# 03_-_PWR_IN.net
KiCad netlist of a schematic drawn in Altium Designer
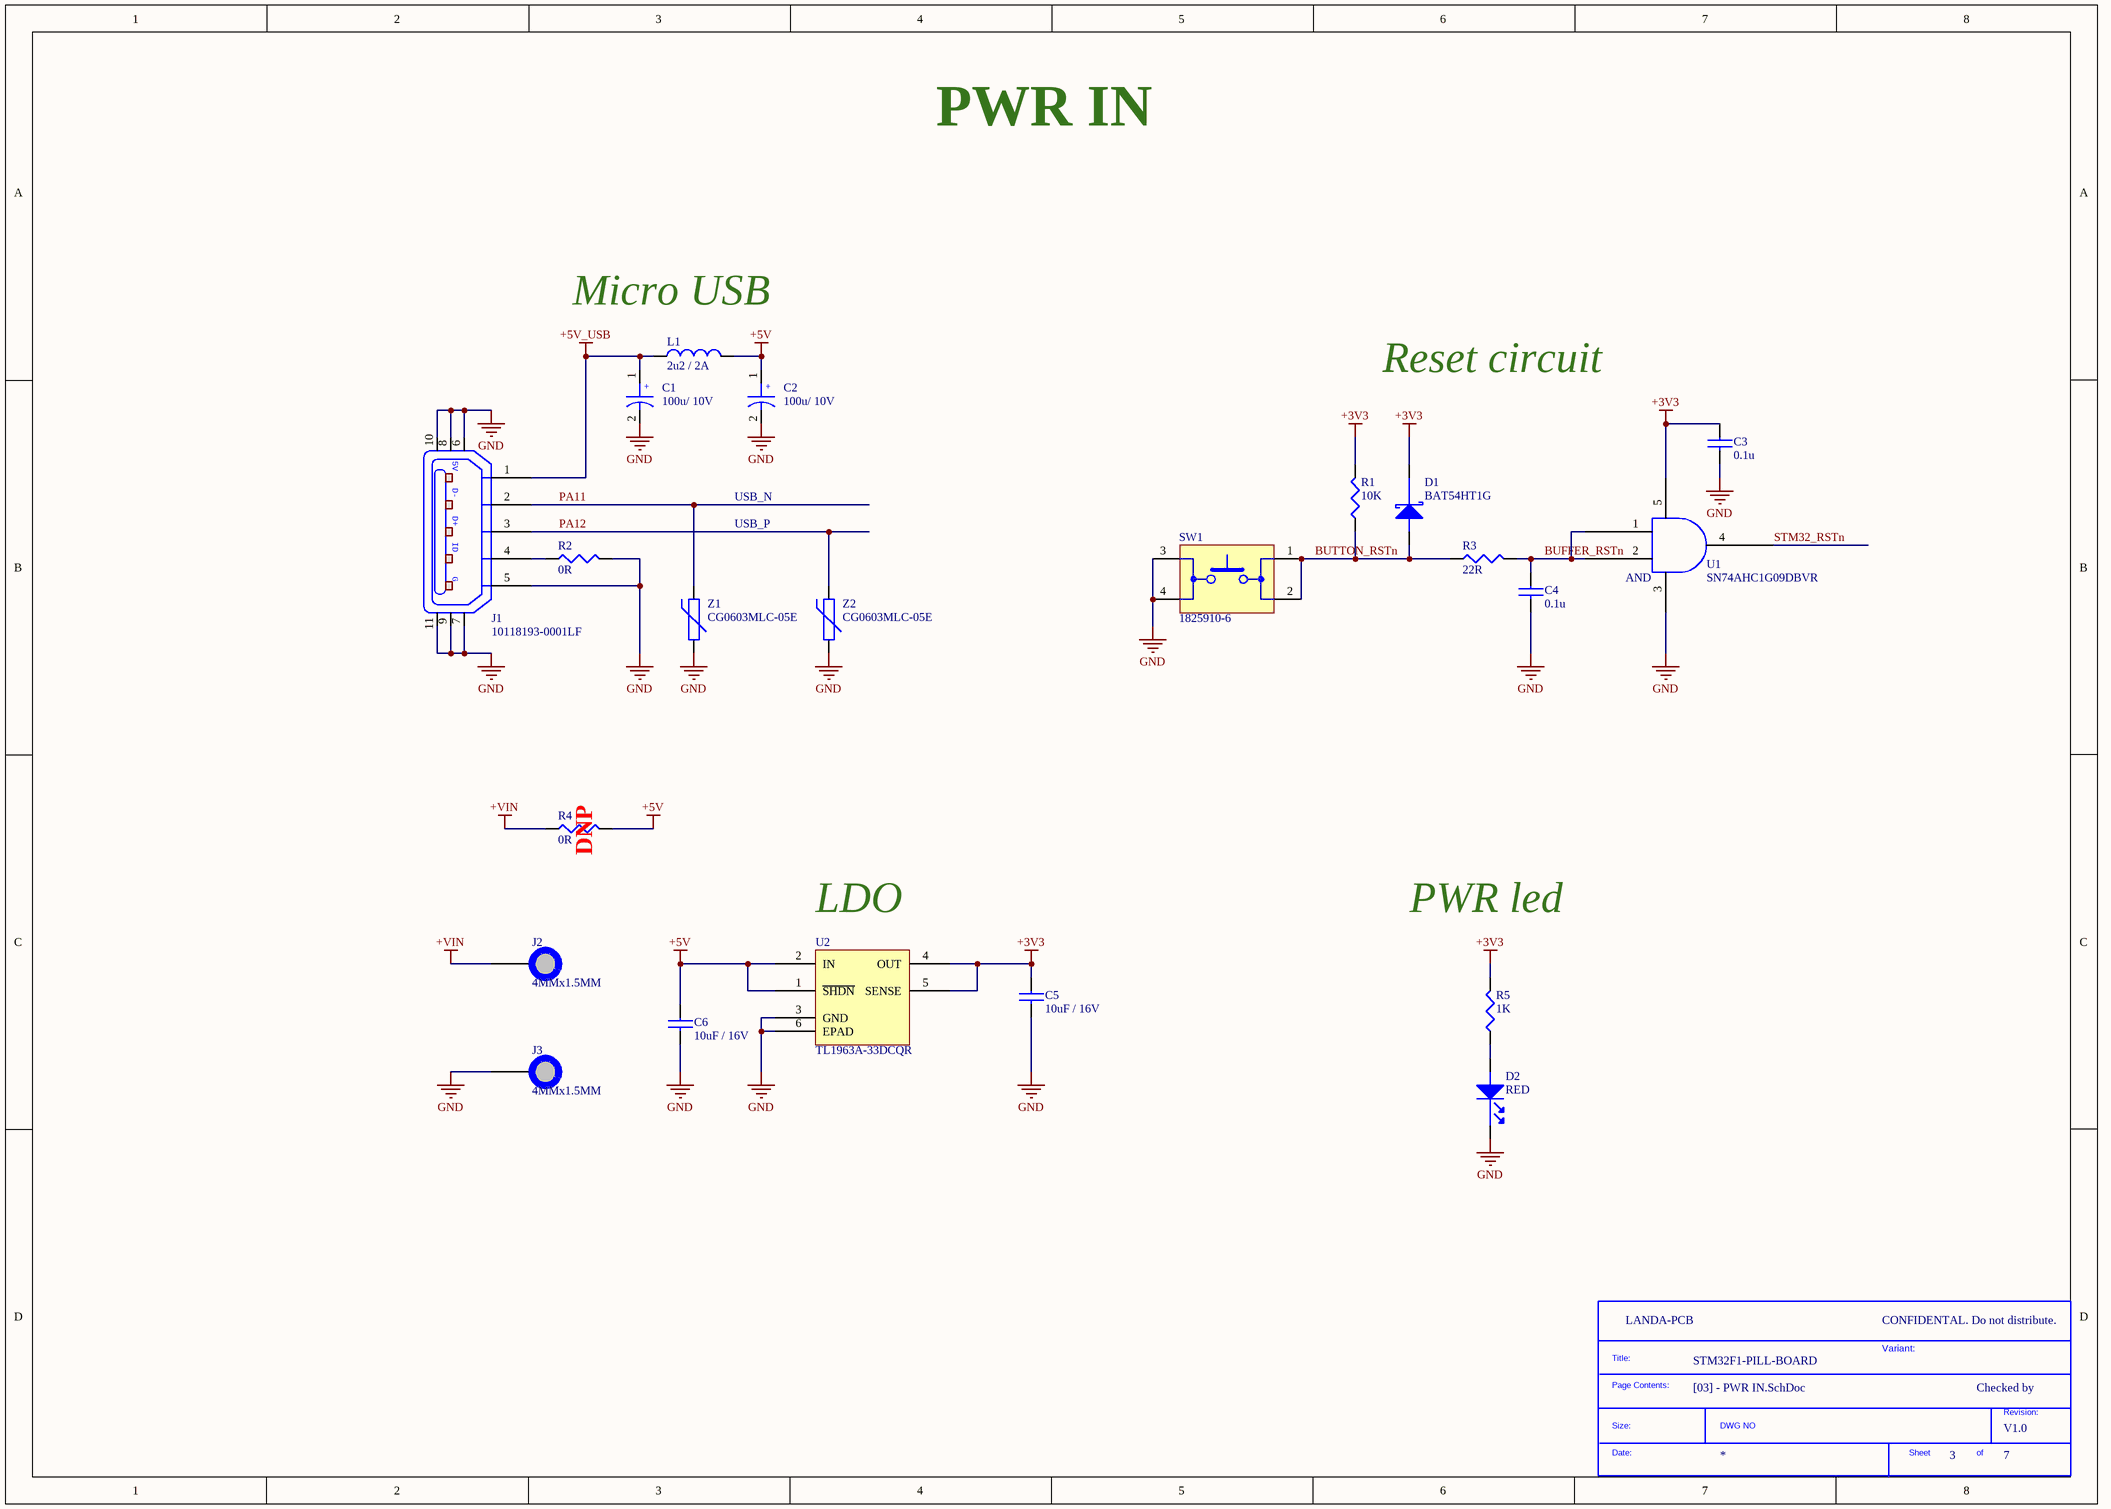
[diagram p0: [03] - PWR IN.SchDoc]

(export (version "E")
  (design (tool "Eeschema 10.0.6"))
  (components
    (comp (ref "C1")
      (value "100u/ 10V")
      (footprint "STM32-PILL-PCB:C_ALU_C_SIZE")
      (description "CAP ALUM 100uF 10V 20% (5 X 5.4mm) SMD")
      (fields
        (field (name "MANUFACTURER") "Panasonic")
        (field (name "MANUFACTURER PART NUMBER") "EEE-1AA101WR")
      )
      (libsource (lib "STM32-PILL-SHC") (part "EEE-1AA101WR"))
    )
    (comp (ref "C2")
      (value "100u/ 10V")
      (footprint "STM32-PILL-PCB:C_ALU_C_SIZE")
      (description "CAP ALUM 100uF 10V 20% (5 X 5.4mm) SMD")
      (fields
        (field (name "MANUFACTURER") "Panasonic")
        (field (name "MANUFACTURER PART NUMBER") "EEE-1AA101WR")
      )
      (libsource (lib "STM32-PILL-SHC") (part "EEE-1AA101WR"))
    )
    (comp (ref "C3")
      (value "0.1u")
      (footprint "STM32-PILL-PCB:C0805")
      (description "CAP CER 0.1UF 50V 10% X7R 0805")
      (fields
        (field (name "MANUFACTURER") "TDK")
        (field (name "MANUFACTURER PART NUMBER") "C2012X7R1H104K085AA")
      )
      (libsource (lib "STM32-PILL-SHC") (part "C2012X7R1H104K085AA"))
    )
    (comp (ref "C4")
      (value "0.1u")
      (footprint "STM32-PILL-PCB:C0805")
      (description "CAP CER 0.1UF 50V 10% X7R 0805")
      (fields
        (field (name "MANUFACTURER") "TDK")
        (field (name "MANUFACTURER PART NUMBER") "C2012X7R1H104K085AA")
      )
      (libsource (lib "STM32-PILL-SHC") (part "C2012X7R1H104K085AA"))
    )
    (comp (ref "C5")
      (value "10uF / 16V")
      (footprint "STM32-PILL-PCB:C0805")
      (description "CAP CER 10 µF, 16 V, 0805, ± 20%, X5R")
      (fields
        (field (name "MANUFACTURER") "TDK")
        (field (name "MANUFACTURER PART NUMBER") "C2012X5R1C106M085AC")
      )
      (libsource (lib "STM32-PILL-SHC") (part "C2012X5R1C106M085AC"))
    )
    (comp (ref "C6")
      (value "10uF / 16V")
      (footprint "STM32-PILL-PCB:C0805")
      (description "CAP CER 10 µF, 16 V, 0805, ± 20%, X5R")
      (fields
        (field (name "MANUFACTURER") "TDK")
        (field (name "MANUFACTURER PART NUMBER") "C2012X5R1C106M085AC")
      )
      (libsource (lib "STM32-PILL-SHC") (part "C2012X5R1C106M085AC"))
    )
    (comp (ref "D1")
      (value "BAT54HT1G")
      (footprint "STM32-PILL-PCB:SOD323")
      (description "DIODE SCHOTTKY 30V 0.2A SOD323")
      (fields (field (name "MANUFACTURER") "ON Semiconductor / Fairchild"))
      (libsource (lib "STM32-PILL-SHC") (part "BAT54HT1G"))
    )
    (comp (ref "D2")
      (value "RED")
      (footprint "STM32-PILL-PCB:LED-0805")
      (description "LED RED 630NM 0805")
      (fields
        (field (name "MANUFACTURER") "Vishay Lite-On")
        (field (name "MANUFACTURER PART NUMBER") "LTST-C170EKT")
      )
      (libsource (lib "STM32-PILL-SHC") (part "LTST-C170EKT"))
    )
    (comp (ref "J1")
      (value "10118193-0001LF")
      (footprint "STM32-PILL-PCB:USB_10118193")
      (description "CONN USB MICRO B RECPT SMT R/A")
      (fields (field (name "MANUFACTURER") "Amphenol FCI"))
      (libsource (lib "STM32-PILL-SHC") (part "10118193-0001LF"))
    )
    (comp (ref "J2")
      (value "4MMx1.5MM")
      (footprint "PAD_WITH_HOLE_4MMx1.5MM")
      (description "Pad with a hole 4mm x 1.5mm")
      (libsource (lib "STM32-PILL-SHC") (part "PAD_WITH_HOLE_4MMx1.5MM"))
    )
    (comp (ref "J3")
      (value "4MMx1.5MM")
      (footprint "PAD_WITH_HOLE_4MMx1.5MM")
      (description "Pad with a hole 4mm x 1.5mm")
      (libsource (lib "STM32-PILL-SHC") (part "PAD_WITH_HOLE_4MMx1.5MM"))
    )
    (comp (ref "L1")
      (value "2u2 / 2A")
      (footprint "STM32-PILL-PCB:C1210_IND")
      (description "FIXED IND 2.2UH 2A 80 MOHM SMD")
      (fields
        (field (name "MANUFACTURER") "KEMET")
        (field (name "MANUFACTURER PART NUMBER") "L1210R2R2MDWIT")
      )
      (libsource (lib "STM32-PILL-SHC") (part "L1210R2R2MDWIT"))
    )
    (comp (ref "R1")
      (value "10K")
      (footprint "STM32-PILL-PCB:R0805")
      (description "RES 10K OHM 1% 1/8W 0805")
      (fields
        (field (name "MANUFACTURER") "Yageo")
        (field (name "MANUFACTURER PART NUMBER") "RC0805FR-0710KL")
      )
      (libsource (lib "STM32-PILL-SHC") (part "RC0805FR-0710KL"))
    )
    (comp (ref "R2")
      (value "0R")
      (footprint "STM32-PILL-PCB:R0805")
      (description "RES 0.0 OHMS, 125 mW, 0805")
      (fields
        (field (name "MANUFACTURER") "Yageo")
        (field (name "MANUFACTURER PART NUMBER") "RC0805JR-070RL")
      )
      (libsource (lib "STM32-PILL-SHC") (part "RC0805JR-070RL"))
    )
    (comp (ref "R3")
      (value "22R")
      (footprint "STM32-PILL-PCB:R0805")
      (description "RES 22 OHM 1% 1/8W 0805")
      (fields
        (field (name "MANUFACTURER") "Yageo")
        (field (name "MANUFACTURER PART NUMBER") "RC0805FR-0722RL")
      )
      (libsource (lib "STM32-PILL-SHC") (part "RC0805FR-0722RL"))
    )
    (comp (ref "R4")
      (value "0R")
      (footprint "STM32-PILL-PCB:R0805")
      (description "RES 0.0 OHMS, 125 mW, 0805")
      (fields
        (field (name "MANUFACTURER") "Yageo")
        (field (name "MANUFACTURER PART NUMBER") "RC0805JR-070RL")
      )
      (libsource (lib "STM32-PILL-SHC") (part "RC0805JR-070RL"))
    )
    (comp (ref "R5")
      (value "1K")
      (footprint "STM32-PILL-PCB:R0805")
      (description "RES 1K OHM 1% 1/8W 0805")
      (fields
        (field (name "MANUFACTURER") "Yageo")
        (field (name "MANUFACTURER PART NUMBER") "RC0805FR-071KL")
      )
      (libsource (lib "STM32-PILL-SHC") (part "RC0805FR-071KL"))
    )
    (comp (ref "SW1")
      (value "1825910-6")
      (footprint "STM32-PILL-PCB:1825910-6")
      (description "SWITCH TACTILE SPST-NO 0.05A 24V")
      (fields (field (name "MANUFACTURER") "TE Connectivity Alcoswitch"))
      (libsource (lib "STM32-PILL-SHC") (part "1825910-6"))
    )
    (comp (ref "U1")
      (value "SN74AHC1G09DBVR")
      (footprint "STM32-PILL-PCB:DBV_SOT_23_5")
      (description "AND GATE 2INP SOT23-5")
      (fields (field (name "MANUFACTURER") "Texas Instruments"))
      (libsource (lib "STM32-PILL-SHC") (part "SN74AHC1G09DBVR"))
    )
    (comp (ref "U2")
      (value "TL1963A-33DCQR")
      (footprint "STM32-PILL-PCB:DCQ (R-PDSO-G6)")
      (description "IC REG LINEAR 3.3V 1.5A SOT223-6")
      (fields (field (name "MANUFACTURER") "Texas Instruments"))
      (libsource (lib "STM32-PILL-SHC") (part "TL1963A-33DCQR"))
    )
    (comp (ref "Z1")
      (value "CG0603MLC-05E")
      (footprint "R0603")
      (description "VARISTOR 0603")
      (fields (field (name "MANUFACTURER") "Bourns") (field (name "VOLTAGE") "5V"))
      (libsource (lib "STM32-PILL-SHC") (part "CG0603MLC-05E"))
    )
    (comp (ref "Z2")
      (value "CG0603MLC-05E")
      (footprint "R0603")
      (description "VARISTOR 0603")
      (fields (field (name "MANUFACTURER") "Bourns") (field (name "VOLTAGE") "5V"))
      (libsource (lib "STM32-PILL-SHC") (part "CG0603MLC-05E"))
    )
  )
  (nets
    (net (code "1") (name "+3V3") (class "Default")
      (node (ref "C3") (pin "1") (pinfunction "1_1") (pintype "passive"))
      (node (ref "C5") (pin "1") (pinfunction "1_1") (pintype "passive"))
      (node (ref "D1") (pin "1") (pinfunction "Cathode_1") (pintype "passive"))
      (node (ref "R1") (pin "2") (pinfunction "2_2") (pintype "passive"))
      (node (ref "R5") (pin "2") (pinfunction "2_2") (pintype "passive"))
      (node (ref "U1") (pin "5") (pinfunction "VCC_5") (pintype "power_in"))
      (node (ref "U2") (pin "4") (pinfunction "OUT_4") (pintype "passive"))
      (node (ref "U2") (pin "5") (pinfunction "SENSE_5") (pintype "passive"))
    )
    (net (code "2") (name "+5V") (class "Default")
      (node (ref "C2") (pin "1") (pinfunction "1_1") (pintype "passive"))
      (node (ref "C6") (pin "1") (pinfunction "1_1") (pintype "passive"))
      (node (ref "L1") (pin "2") (pinfunction "2_2") (pintype "passive"))
      (node (ref "R4") (pin "2") (pinfunction "2_2") (pintype "passive"))
      (node (ref "U2") (pin "1") (pinfunction "~{SHDN}_1") (pintype "passive"))
      (node (ref "U2") (pin "2") (pinfunction "IN_2") (pintype "passive"))
    )
    (net (code "3") (name "+5V_USB") (class "Default")
      (node (ref "C1") (pin "1") (pinfunction "1_1") (pintype "passive"))
      (node (ref "J1") (pin "1") (pinfunction "P1_1") (pintype "passive"))
      (node (ref "L1") (pin "1") (pinfunction "1_1") (pintype "passive"))
    )
    (net (code "4") (name "+VIN") (class "Default")
      (node (ref "J2") (pin "1") (pinfunction "1_1") (pintype "passive"))
      (node (ref "R4") (pin "1") (pinfunction "1_1") (pintype "passive"))
    )
    (net (code "5") (name "/BUFFER_RSTn") (class "Default")
      (node (ref "C4") (pin "1") (pinfunction "1_1") (pintype "passive"))
      (node (ref "R3") (pin "2") (pinfunction "2_2") (pintype "passive"))
      (node (ref "U1") (pin "1") (pinfunction "A_1") (pintype "passive"))
      (node (ref "U1") (pin "2") (pinfunction "B_2") (pintype "passive"))
    )
    (net (code "6") (name "/BUTTON_RSTn") (class "Default")
      (node (ref "D1") (pin "2") (pinfunction "Anode_2") (pintype "passive"))
      (node (ref "R1") (pin "1") (pinfunction "1_1") (pintype "passive"))
      (node (ref "R3") (pin "1") (pinfunction "1_1") (pintype "passive"))
      (node (ref "SW1") (pin "1") (pinfunction "1_1") (pintype "passive"))
      (node (ref "SW1") (pin "2") (pinfunction "2_2") (pintype "passive"))
    )
    (net (code "7") (name "/PA11") (class "Default")
      (node (ref "J1") (pin "2") (pinfunction "P2_2") (pintype "passive"))
      (node (ref "Z1") (pin "2") (pinfunction "2_2") (pintype "passive"))
    )
    (net (code "8") (name "/PA12") (class "Default")
      (node (ref "J1") (pin "3") (pinfunction "P3_3") (pintype "passive"))
      (node (ref "Z2") (pin "2") (pinfunction "2_2") (pintype "passive"))
    )
    (net (code "9") (name "/STM32_RSTn") (class "Default")
      (node (ref "U1") (pin "4") (pinfunction "Y_4") (pintype "passive"))
    )
    (net (code "10") (name "GND") (class "Default")
      (node (ref "C1") (pin "2") (pinfunction "2_2") (pintype "passive"))
      (node (ref "C2") (pin "2") (pinfunction "2_2") (pintype "passive"))
      (node (ref "C3") (pin "2") (pinfunction "2_2") (pintype "passive"))
      (node (ref "C4") (pin "2") (pinfunction "2_2") (pintype "passive"))
      (node (ref "C5") (pin "2") (pinfunction "2_2") (pintype "passive"))
      (node (ref "C6") (pin "2") (pinfunction "2_2") (pintype "passive"))
      (node (ref "D2") (pin "1") (pinfunction "cathode_1") (pintype "passive"))
      (node (ref "J1") (pin "10") (pinfunction "10_10") (pintype "passive"))
      (node (ref "J1") (pin "11") (pinfunction "11_11") (pintype "passive"))
      (node (ref "J1") (pin "5") (pinfunction "P5_5") (pintype "passive"))
      (node (ref "J1") (pin "6") (pinfunction "6_6") (pintype "passive"))
      (node (ref "J1") (pin "7") (pinfunction "7_7") (pintype "passive"))
      (node (ref "J1") (pin "8") (pinfunction "8_8") (pintype "passive"))
      (node (ref "J1") (pin "9") (pinfunction "9_9") (pintype "passive"))
      (node (ref "J3") (pin "1") (pinfunction "1_1") (pintype "passive"))
      (node (ref "R2") (pin "2") (pinfunction "2_2") (pintype "passive"))
      (node (ref "SW1") (pin "3") (pinfunction "MECH1_3") (pintype "passive"))
      (node (ref "SW1") (pin "4") (pinfunction "MECH2_4") (pintype "passive"))
      (node (ref "U1") (pin "3") (pinfunction "GND_3") (pintype "power_in"))
      (node (ref "U2") (pin "3") (pinfunction "GND_3") (pintype "passive"))
      (node (ref "U2") (pin "6") (pinfunction "EPAD_6") (pintype "passive"))
      (node (ref "Z1") (pin "1") (pinfunction "1_1") (pintype "passive"))
      (node (ref "Z2") (pin "1") (pinfunction "1_1") (pintype "passive"))
    )
    (net (code "11") (name "Net-(D2-ANODE)") (class "Default")
      (node (ref "D2") (pin "2") (pinfunction "ANODE_2") (pintype "passive"))
      (node (ref "R5") (pin "1") (pinfunction "1_1") (pintype "passive"))
    )
    (net (code "12") (name "Net-(J1-P4)") (class "Default")
      (node (ref "J1") (pin "4") (pinfunction "P4_4") (pintype "passive"))
      (node (ref "R2") (pin "1") (pinfunction "1_1") (pintype "passive"))
    )
  )
)
